# STM32F103C8T6.net
KiCad netlist of a schematic drawn in Altium Designer
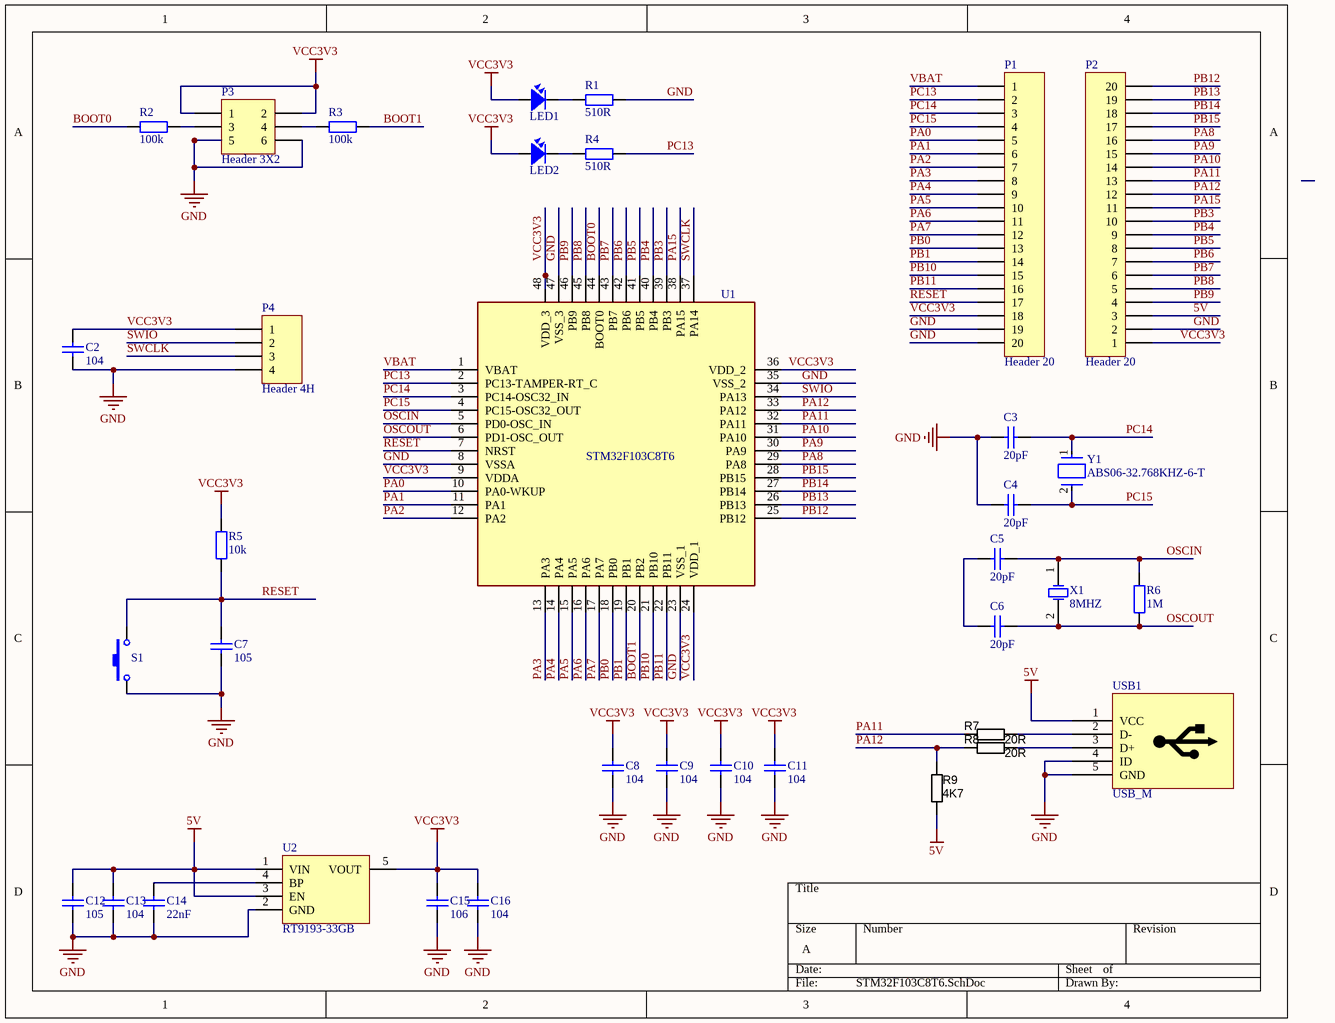
[diagram p0: STM32F103C8T6.SchDoc]

(export (version "E")
  (design (tool "Eeschema 10.0.6"))
  (components
    (comp (ref "C2")
      (value "104")
      (footprint "tu 0603")
      (description "Dán")
      (libsource (lib "Capacitor") (part "Tu 0603 104 50V 10%"))
    )
    (comp (ref "C3")
      (value "20pF")
      (footprint "tu 0805")
      (description "Dán")
      (libsource (lib "Capacitor") (part "Tu 0805 20pF 50V 10%"))
    )
    (comp (ref "C4")
      (value "20pF")
      (footprint "tu 0805")
      (description "Dán")
      (libsource (lib "Capacitor") (part "Tu 0805 20pF 50V 10%"))
    )
    (comp (ref "C5")
      (value "20pF")
      (footprint "tu 0805")
      (description "Dán")
      (libsource (lib "Capacitor") (part "Tu 0805 20pF 50V 10%"))
    )
    (comp (ref "C6")
      (value "20pF")
      (footprint "tu 0805")
      (description "Dán")
      (libsource (lib "Capacitor") (part "Tu 0805 20pF 50V 10%"))
    )
    (comp (ref "C7")
      (value "105")
      (footprint "tu 0603")
      (description "Dán")
      (libsource (lib "Capacitor") (part "Tu 0603 105 16V 20%"))
    )
    (comp (ref "C8")
      (value "104")
      (footprint "tu 0603")
      (description "Dán")
      (libsource (lib "Capacitor") (part "Tu 0603 104 50V 10%"))
    )
    (comp (ref "C9")
      (value "104")
      (footprint "tu 0603")
      (description "Dán")
      (libsource (lib "Capacitor") (part "Tu 0603 104 50V 10%"))
    )
    (comp (ref "C10")
      (value "104")
      (footprint "tu 0603")
      (description "Dán")
      (libsource (lib "Capacitor") (part "Tu 0603 104 50V 10%"))
    )
    (comp (ref "C11")
      (value "104")
      (footprint "tu 0603")
      (description "Dán")
      (libsource (lib "Capacitor") (part "Tu 0603 104 50V 10%"))
    )
    (comp (ref "C12")
      (value "105")
      (footprint "tu 0805")
      (description "Dán")
      (libsource (lib "Capacitor") (part "Tu 0805 105 50V 10%"))
    )
    (comp (ref "C13")
      (value "104")
      (footprint "tu 0603")
      (description "Dán")
      (libsource (lib "Capacitor") (part "Tu 0603 104 50V 10%"))
    )
    (comp (ref "C14")
      (value "22nF")
      (footprint "tu 0805")
      (description "Dán")
      (libsource (lib "Capacitor") (part "Tu 0805 22nF 50V 20%"))
    )
    (comp (ref "C15")
      (value "106")
      (footprint "tu 0603")
      (description "Dán")
      (libsource (lib "Capacitor") (part "Tu 0603 106 16V 20%"))
    )
    (comp (ref "C16")
      (value "104")
      (footprint "tu 0603")
      (description "Dán")
      (libsource (lib "Capacitor") (part "Tu 0603 104 50V 10%"))
    )
    (comp (ref "LED1")
      (value "LED SMD")
      (footprint "SM-LED-0805-Blue")
      (libsource (lib "syhaunguyen") (part "LED-SMD-0805"))
    )
    (comp (ref "LED2")
      (value "LED SMD")
      (footprint "SM-LED-0805-Blue")
      (libsource (lib "syhaunguyen") (part "LED-SMD-0805"))
    )
    (comp (ref "P1")
      (value "Header 20")
      (footprint "HDR1X20")
      (description "Header, 20-Pin")
      (fields (field (name "PUBLISHER") "Altium Limited"))
      (libsource (lib "KhanhBK_SCH_Library_2") (part "Header 20"))
    )
    (comp (ref "P2")
      (value "Header 20")
      (footprint "HDR1X20")
      (description "Header, 20-Pin")
      (fields (field (name "PUBLISHER") "Altium Limited"))
      (libsource (lib "") (part "Header 20_1"))
    )
    (comp (ref "P3")
      (value "Header 3X2")
      (footprint "HDR2X3")
      (description "Header, 3-Pin, Dual row")
      (fields (field (name "PUBLISHER") "Altium Limited"))
      (libsource (lib "KhanhBK_SCH_Library_2") (part "Header 3X2"))
    )
    (comp (ref "P4")
      (value "Header 4H")
      (footprint "HDR1X4H")
      (description "Header, 4-Pin, Right Angle")
      (fields (field (name "PUBLISHER") "Altium Limited"))
      (libsource (lib "KhanhBK_SCH_Library_2") (part "Header 4H"))
    )
    (comp (ref "R1")
      (value "510R")
      (footprint "tro smd 0603")
      (description "Dán")
      (libsource (lib "Resistor") (part "Tro 0603 5% 510R"))
    )
    (comp (ref "R2")
      (value "100k")
      (footprint "tro smd 0603")
      (description "Dán")
      (libsource (lib "Resistor") (part "Tro 0603 5% 100k"))
    )
    (comp (ref "R3")
      (value "100k")
      (footprint "tro smd 0603")
      (description "Dán")
      (libsource (lib "Resistor") (part "Tro 0603 5% 100k"))
    )
    (comp (ref "R4")
      (value "510R")
      (footprint "tro smd 0603")
      (description "Dán")
      (libsource (lib "Resistor") (part "Tro 0603 5% 510R"))
    )
    (comp (ref "R5")
      (value "10k")
      (footprint "tro smd 0603")
      (description "Dán")
      (libsource (lib "Resistor") (part "Tro 0603 1% 10k"))
    )
    (comp (ref "R6")
      (value "1M")
      (footprint "tro smd 0603")
      (description "Dán")
      (libsource (lib "Resistor") (part "Tro 0603 5% 1M"))
    )
    (comp (ref "R7")
      (value "20R")
      (footprint "RESC3216N")
      (description "Resistor SMD chip 20 Ohm 0.25W 5% 1206")
      (fields (field (name "TOLERANCE") "±5%") (field (name "Comment") "Thick Film"))
      (libsource (lib "PBL - Resistors") (part "RES_20R_1206_5%"))
    )
    (comp (ref "R8")
      (value "20R")
      (footprint "RESC3216N")
      (description "Resistor SMD chip 20 Ohm 0.25W 5% 1206")
      (fields (field (name "TOLERANCE") "±5%") (field (name "Comment") "Thick Film"))
      (libsource (lib "PBL - Resistors") (part "RES_20R_1206_5%"))
    )
    (comp (ref "R9")
      (value "4K7")
      (footprint "RESC1608N")
      (description "Resistor SMD chip 4.7k Ohm 0.1W 5% 0603")
      (fields (field (name "TOLERANCE") "±5%") (field (name "Comment") "Thick Film"))
      (libsource (lib "PBL - Resistors") (part "RES_4K7_0603_5%"))
    )
    (comp (ref "S1")
      (value "SW-SMD")
      (footprint "SW-SMD")
      (description "Switch")
      (fields (field (name "PUBLISHER") "Altium Limited"))
      (libsource (lib "KhanhBK_SCH_Library_2") (part "SW-SMD"))
    )
    (comp (ref "U1")
      (value "STM32F103C8T6")
      (footprint "LQFP-48_19.6_393_58X11_SMD")
      (description "ARM® Cortex®-M3 STM32F1 Microcontroller IC 32-Bit 72MHz 64KB (64K x 8) FLASH 48-LQFP (7x7)")
      (fields (field (name "MANUFACTURER") "STMicroelectronics"))
      (libsource (lib "IC") (part "IC_STM32F103C8T6"))
    )
    (comp (ref "U2")
      (value "RT9193-33GB")
      (footprint "SOT23-5")
      (description "Linear Voltage Regulator IC 1 Output 300mA SOT-23-5")
      (fields (field (name "MANUFACTURER") "Richtek USA Inc."))
      (libsource (lib "IC") (part "REG_5.5V-3.3V-0.3A-1W-SOT-23-5"))
    )
    (comp (ref "USB1")
      (value "USB_M")
      (footprint "USB_B_MINI_SMD")
      (libsource (lib "KhanhBK_SCH_Library_2") (part "USB_M"))
    )
    (comp (ref "X1")
      (value "8MHZ")
      (footprint "ABRA-ABLS-14.7456MHZ-B2-T_V")
      (description "Low Profile Crystal, 8.0 MHz, +/- 30 ppm, -20 to 70 degC, 2-Pin SMD, RoHS, Tape and Reel")
      (fields (field (name "MANUFACTURER") "ABRACON") (field (name "TOLERANCE") "30PPM"))
      (libsource (lib "Altium Content Vault") (part "XTAL_1-2-2"))
    )
    (comp (ref "Y1")
      (value "ABS06-32.768KHZ-6-T")
      (footprint "FP-ABS06-MFG")
      (description "Crystal 32.768kHz ±20ppm (Tol) 6pF FUND 90kΩ 2-Pin Mini-CSMD T/R")
      (libsource (lib "Altium Content Vault") (part "c23a69dc6c9e2f18f2079038eb95dd1"))
    )
  )
  (nets
    (net (code "1") (name "/BOOT0") (class "Default")
      (node (ref "R2") (pin "1") (pinfunction "1_1") (pintype "passive"))
      (node (ref "U1") (pin "44") (pinfunction "BOOT0_44") (pintype "passive"))
    )
    (net (code "2") (name "/BOOT1") (class "Default")
      (node (ref "R3") (pin "2") (pinfunction "2_2") (pintype "passive"))
      (node (ref "U1") (pin "20") (pinfunction "PB2_20") (pintype "passive"))
    )
    (net (code "3") (name "/OSCIN") (class "Default")
      (node (ref "C5") (pin "1") (pinfunction "1_1") (pintype "passive"))
      (node (ref "R6") (pin "2") (pinfunction "2_2") (pintype "passive"))
      (node (ref "U1") (pin "5") (pinfunction "PD0-OSC_IN_5") (pintype "passive"))
      (node (ref "X1") (pin "1") (pinfunction "X1_1") (pintype "passive"))
    )
    (net (code "4") (name "/OSCOUT") (class "Default")
      (node (ref "C6") (pin "1") (pinfunction "1_1") (pintype "passive"))
      (node (ref "R6") (pin "1") (pinfunction "1_1") (pintype "passive"))
      (node (ref "U1") (pin "6") (pinfunction "PD1-OSC_OUT_6") (pintype "passive"))
      (node (ref "X1") (pin "2") (pinfunction "X2_2") (pintype "passive"))
    )
    (net (code "5") (name "/PA0") (class "Default")
      (node (ref "P1") (pin "5") (pinfunction "5_5") (pintype "passive"))
      (node (ref "U1") (pin "10") (pinfunction "PA0-WKUP_10") (pintype "passive"))
    )
    (net (code "6") (name "/PA1") (class "Default")
      (node (ref "P1") (pin "6") (pinfunction "6_6") (pintype "passive"))
      (node (ref "U1") (pin "11") (pinfunction "PA1_11") (pintype "passive"))
    )
    (net (code "7") (name "/PA2") (class "Default")
      (node (ref "P1") (pin "7") (pinfunction "7_7") (pintype "passive"))
      (node (ref "U1") (pin "12") (pinfunction "PA2_12") (pintype "passive"))
    )
    (net (code "8") (name "/PA3") (class "Default")
      (node (ref "P1") (pin "8") (pinfunction "8_8") (pintype "passive"))
      (node (ref "U1") (pin "13") (pinfunction "PA3_13") (pintype "passive"))
    )
    (net (code "9") (name "/PA4") (class "Default")
      (node (ref "P1") (pin "9") (pinfunction "9_9") (pintype "passive"))
      (node (ref "U1") (pin "14") (pinfunction "PA4_14") (pintype "passive"))
    )
    (net (code "10") (name "/PA5") (class "Default")
      (node (ref "P1") (pin "10") (pinfunction "10_10") (pintype "passive"))
      (node (ref "U1") (pin "15") (pinfunction "PA5_15") (pintype "passive"))
    )
    (net (code "11") (name "/PA6") (class "Default")
      (node (ref "P1") (pin "11") (pinfunction "11_11") (pintype "passive"))
      (node (ref "U1") (pin "16") (pinfunction "PA6_16") (pintype "passive"))
    )
    (net (code "12") (name "/PA7") (class "Default")
      (node (ref "P1") (pin "12") (pinfunction "12_12") (pintype "passive"))
      (node (ref "U1") (pin "17") (pinfunction "PA7_17") (pintype "passive"))
    )
    (net (code "13") (name "/PA8") (class "Default")
      (node (ref "P2") (pin "16") (pinfunction "16_16") (pintype "passive"))
      (node (ref "U1") (pin "29") (pinfunction "PA8_29") (pintype "passive"))
    )
    (net (code "14") (name "/PA9") (class "Default")
      (node (ref "P2") (pin "15") (pinfunction "15_15") (pintype "passive"))
      (node (ref "U1") (pin "30") (pinfunction "PA9_30") (pintype "passive"))
    )
    (net (code "15") (name "/PA10") (class "Default")
      (node (ref "P2") (pin "14") (pinfunction "14_14") (pintype "passive"))
      (node (ref "U1") (pin "31") (pinfunction "PA10_31") (pintype "passive"))
    )
    (net (code "16") (name "/PA11") (class "Default")
      (node (ref "P2") (pin "13") (pinfunction "13_13") (pintype "passive"))
      (node (ref "R7") (pin "1") (pinfunction "1_1") (pintype "passive"))
      (node (ref "U1") (pin "32") (pinfunction "PA11_32") (pintype "passive"))
    )
    (net (code "17") (name "/PA12") (class "Default")
      (node (ref "P2") (pin "12") (pinfunction "12_12") (pintype "passive"))
      (node (ref "R8") (pin "1") (pinfunction "1_1") (pintype "passive"))
      (node (ref "R9") (pin "1") (pinfunction "1_1") (pintype "passive"))
      (node (ref "U1") (pin "33") (pinfunction "PA12_33") (pintype "passive"))
    )
    (net (code "18") (name "/PA15") (class "Default")
      (node (ref "P2") (pin "11") (pinfunction "11_11") (pintype "passive"))
      (node (ref "U1") (pin "38") (pinfunction "PA15_38") (pintype "passive"))
    )
    (net (code "19") (name "/PB0") (class "Default")
      (node (ref "P1") (pin "13") (pinfunction "13_13") (pintype "passive"))
      (node (ref "U1") (pin "18") (pinfunction "PB0_18") (pintype "passive"))
    )
    (net (code "20") (name "/PB1") (class "Default")
      (node (ref "P1") (pin "14") (pinfunction "14_14") (pintype "passive"))
      (node (ref "U1") (pin "19") (pinfunction "PB1_19") (pintype "passive"))
    )
    (net (code "21") (name "/PB3") (class "Default")
      (node (ref "P2") (pin "10") (pinfunction "10_10") (pintype "passive"))
      (node (ref "U1") (pin "39") (pinfunction "PB3_39") (pintype "passive"))
    )
    (net (code "22") (name "/PB4") (class "Default")
      (node (ref "P2") (pin "9") (pinfunction "9_9") (pintype "passive"))
      (node (ref "U1") (pin "40") (pinfunction "PB4_40") (pintype "passive"))
    )
    (net (code "23") (name "/PB5") (class "Default")
      (node (ref "P2") (pin "8") (pinfunction "8_8") (pintype "passive"))
      (node (ref "U1") (pin "41") (pinfunction "PB5_41") (pintype "passive"))
    )
    (net (code "24") (name "/PB6") (class "Default")
      (node (ref "P2") (pin "7") (pinfunction "7_7") (pintype "passive"))
      (node (ref "U1") (pin "42") (pinfunction "PB6_42") (pintype "passive"))
    )
    (net (code "25") (name "/PB7") (class "Default")
      (node (ref "P2") (pin "6") (pinfunction "6_6") (pintype "passive"))
      (node (ref "U1") (pin "43") (pinfunction "PB7_43") (pintype "passive"))
    )
    (net (code "26") (name "/PB8") (class "Default")
      (node (ref "P2") (pin "5") (pinfunction "5_5") (pintype "passive"))
      (node (ref "U1") (pin "45") (pinfunction "PB8_45") (pintype "passive"))
    )
    (net (code "27") (name "/PB9") (class "Default")
      (node (ref "P2") (pin "4") (pinfunction "4_4") (pintype "passive"))
      (node (ref "U1") (pin "46") (pinfunction "PB9_46") (pintype "passive"))
    )
    (net (code "28") (name "/PB10") (class "Default")
      (node (ref "P1") (pin "15") (pinfunction "15_15") (pintype "passive"))
      (node (ref "U1") (pin "21") (pinfunction "PB10_21") (pintype "passive"))
    )
    (net (code "29") (name "/PB11") (class "Default")
      (node (ref "P1") (pin "16") (pinfunction "16_16") (pintype "passive"))
      (node (ref "U1") (pin "22") (pinfunction "PB11_22") (pintype "passive"))
    )
    (net (code "30") (name "/PB12") (class "Default")
      (node (ref "P2") (pin "20") (pinfunction "20_20") (pintype "passive"))
      (node (ref "U1") (pin "25") (pinfunction "PB12_25") (pintype "passive"))
    )
    (net (code "31") (name "/PB13") (class "Default")
      (node (ref "P2") (pin "19") (pinfunction "19_19") (pintype "passive"))
      (node (ref "U1") (pin "26") (pinfunction "PB13_26") (pintype "passive"))
    )
    (net (code "32") (name "/PB14") (class "Default")
      (node (ref "P2") (pin "18") (pinfunction "18_18") (pintype "passive"))
      (node (ref "U1") (pin "27") (pinfunction "PB14_27") (pintype "passive"))
    )
    (net (code "33") (name "/PB15") (class "Default")
      (node (ref "P2") (pin "17") (pinfunction "17_17") (pintype "passive"))
      (node (ref "U1") (pin "28") (pinfunction "PB15_28") (pintype "passive"))
    )
    (net (code "34") (name "/PC13") (class "Default")
      (node (ref "P1") (pin "2") (pinfunction "2_2") (pintype "passive"))
      (node (ref "R4") (pin "2") (pinfunction "2_2") (pintype "passive"))
      (node (ref "U1") (pin "2") (pinfunction "PC13-TAMPER-RT_C_2") (pintype "passive"))
    )
    (net (code "35") (name "/PC14") (class "Default")
      (node (ref "C3") (pin "1") (pinfunction "1_1") (pintype "passive"))
      (node (ref "P1") (pin "3") (pinfunction "3_3") (pintype "passive"))
      (node (ref "U1") (pin "3") (pinfunction "PC14-OSC32_IN_3") (pintype "passive"))
      (node (ref "Y1") (pin "1") (pinfunction "1_1") (pintype "passive"))
    )
    (net (code "36") (name "/PC15") (class "Default")
      (node (ref "C4") (pin "1") (pinfunction "1_1") (pintype "passive"))
      (node (ref "P1") (pin "4") (pinfunction "4_4") (pintype "passive"))
      (node (ref "U1") (pin "4") (pinfunction "PC15-OSC32_OUT_4") (pintype "passive"))
      (node (ref "Y1") (pin "2") (pinfunction "2_2") (pintype "passive"))
    )
    (net (code "37") (name "/RESET") (class "Default")
      (node (ref "C7") (pin "1") (pinfunction "1_1") (pintype "passive"))
      (node (ref "P1") (pin "17") (pinfunction "17_17") (pintype "passive"))
      (node (ref "R5") (pin "1") (pinfunction "1_1") (pintype "passive"))
      (node (ref "S1") (pin "2") (pinfunction "2_2") (pintype "passive"))
      (node (ref "U1") (pin "7") (pinfunction "NRST_7") (pintype "passive"))
    )
    (net (code "38") (name "/SWCLK") (class "Default")
      (node (ref "P4") (pin "3") (pinfunction "3_3") (pintype "passive"))
      (node (ref "U1") (pin "37") (pinfunction "PA14_37") (pintype "passive"))
    )
    (net (code "39") (name "/SWIO") (class "Default")
      (node (ref "P4") (pin "2") (pinfunction "2_2") (pintype "passive"))
      (node (ref "U1") (pin "34") (pinfunction "PA13_34") (pintype "passive"))
    )
    (net (code "40") (name "/VBAT") (class "Default")
      (node (ref "P1") (pin "1") (pinfunction "1_1") (pintype "passive"))
      (node (ref "U1") (pin "1") (pinfunction "VBAT_1") (pintype "passive"))
    )
    (net (code "41") (name "5V") (class "Default")
      (node (ref "C12") (pin "1") (pinfunction "1_1") (pintype "passive"))
      (node (ref "C13") (pin "1") (pinfunction "1_1") (pintype "passive"))
      (node (ref "P2") (pin "3") (pinfunction "3_3") (pintype "passive"))
      (node (ref "R9") (pin "2") (pinfunction "2_2") (pintype "passive"))
      (node (ref "U2") (pin "1") (pinfunction "VIN_1") (pintype "passive"))
      (node (ref "U2") (pin "3") (pinfunction "EN_3") (pintype "passive"))
      (node (ref "USB1") (pin "1") (pinfunction "VCC_1") (pintype "passive"))
    )
    (net (code "42") (name "GND") (class "Default")
      (node (ref "C10") (pin "2") (pinfunction "2_2") (pintype "passive"))
      (node (ref "C11") (pin "2") (pinfunction "2_2") (pintype "passive"))
      (node (ref "C12") (pin "2") (pinfunction "2_2") (pintype "passive"))
      (node (ref "C13") (pin "2") (pinfunction "2_2") (pintype "passive"))
      (node (ref "C14") (pin "2") (pinfunction "2_2") (pintype "passive"))
      (node (ref "C15") (pin "2") (pinfunction "2_2") (pintype "passive"))
      (node (ref "C16") (pin "2") (pinfunction "2_2") (pintype "passive"))
      (node (ref "C2") (pin "2") (pinfunction "2_2") (pintype "passive"))
      (node (ref "C3") (pin "2") (pinfunction "2_2") (pintype "passive"))
      (node (ref "C4") (pin "2") (pinfunction "2_2") (pintype "passive"))
      (node (ref "C7") (pin "2") (pinfunction "2_2") (pintype "passive"))
      (node (ref "C8") (pin "2") (pinfunction "2_2") (pintype "passive"))
      (node (ref "C9") (pin "2") (pinfunction "2_2") (pintype "passive"))
      (node (ref "P1") (pin "19") (pinfunction "19_19") (pintype "passive"))
      (node (ref "P1") (pin "20") (pinfunction "20_20") (pintype "passive"))
      (node (ref "P2") (pin "2") (pinfunction "2_2") (pintype "passive"))
      (node (ref "P3") (pin "5") (pinfunction "5_5") (pintype "passive"))
      (node (ref "P3") (pin "6") (pinfunction "6_6") (pintype "passive"))
      (node (ref "P4") (pin "4") (pinfunction "4_4") (pintype "passive"))
      (node (ref "R1") (pin "2") (pinfunction "2_2") (pintype "passive"))
      (node (ref "S1") (pin "1") (pinfunction "1_1") (pintype "passive"))
      (node (ref "U1") (pin "23") (pinfunction "VSS_1_23") (pintype "passive"))
      (node (ref "U1") (pin "35") (pinfunction "VSS_2_35") (pintype "passive"))
      (node (ref "U1") (pin "47") (pinfunction "VSS_3_47") (pintype "passive"))
      (node (ref "U1") (pin "8") (pinfunction "VSSA_8") (pintype "passive"))
      (node (ref "U2") (pin "2") (pinfunction "GND_2") (pintype "passive"))
      (node (ref "USB1") (pin "4") (pinfunction "ID_4") (pintype "passive"))
      (node (ref "USB1") (pin "5") (pinfunction "GND_5") (pintype "passive"))
    )
    (net (code "43") (name "Net-(C5-Pad2)") (class "Default")
      (node (ref "C5") (pin "2") (pinfunction "2_2") (pintype "passive"))
      (node (ref "C6") (pin "2") (pinfunction "2_2") (pintype "passive"))
    )
    (net (code "44") (name "Net-(LED1-Pad2)") (class "Default")
      (node (ref "LED1") (pin "2") (pinfunction "2_2") (pintype "passive"))
      (node (ref "R1") (pin "1") (pinfunction "1_1") (pintype "passive"))
    )
    (net (code "45") (name "Net-(LED2-Pad2)") (class "Default")
      (node (ref "LED2") (pin "2") (pinfunction "2_2") (pintype "passive"))
      (node (ref "R4") (pin "1") (pinfunction "1_1") (pintype "passive"))
    )
    (net (code "46") (name "Net-(P3-Pad3)") (class "Default")
      (node (ref "P3") (pin "3") (pinfunction "3_3") (pintype "passive"))
      (node (ref "R2") (pin "2") (pinfunction "2_2") (pintype "passive"))
    )
    (net (code "47") (name "Net-(P3-Pad4)") (class "Default")
      (node (ref "P3") (pin "4") (pinfunction "4_4") (pintype "passive"))
      (node (ref "R3") (pin "1") (pinfunction "1_1") (pintype "passive"))
    )
    (net (code "48") (name "Net-(U2-BP)") (class "Default")
      (node (ref "C14") (pin "1") (pinfunction "1_1") (pintype "passive"))
      (node (ref "U2") (pin "4") (pinfunction "BP_4") (pintype "passive"))
    )
    (net (code "49") (name "Net-(USB1-D+)") (class "Default")
      (node (ref "R8") (pin "2") (pinfunction "2_2") (pintype "passive"))
      (node (ref "USB1") (pin "3") (pinfunction "D+_3") (pintype "passive"))
    )
    (net (code "50") (name "Net-(USB1-D-)") (class "Default")
      (node (ref "R7") (pin "2") (pinfunction "2_2") (pintype "passive"))
      (node (ref "USB1") (pin "2") (pinfunction "D-_2") (pintype "passive"))
    )
    (net (code "51") (name "VCC3V3") (class "Default")
      (node (ref "C10") (pin "1") (pinfunction "1_1") (pintype "passive"))
      (node (ref "C11") (pin "1") (pinfunction "1_1") (pintype "passive"))
      (node (ref "C15") (pin "1") (pinfunction "1_1") (pintype "passive"))
      (node (ref "C16") (pin "1") (pinfunction "1_1") (pintype "passive"))
      (node (ref "C2") (pin "1") (pinfunction "1_1") (pintype "passive"))
      (node (ref "C8") (pin "1") (pinfunction "1_1") (pintype "passive"))
      (node (ref "C9") (pin "1") (pinfunction "1_1") (pintype "passive"))
      (node (ref "LED1") (pin "1") (pinfunction "1_1") (pintype "passive"))
      (node (ref "LED2") (pin "1") (pinfunction "1_1") (pintype "passive"))
      (node (ref "P1") (pin "18") (pinfunction "18_18") (pintype "passive"))
      (node (ref "P2") (pin "1") (pinfunction "1_1") (pintype "passive"))
      (node (ref "P3") (pin "1") (pinfunction "1_1") (pintype "passive"))
      (node (ref "P3") (pin "2") (pinfunction "2_2") (pintype "passive"))
      (node (ref "P4") (pin "1") (pinfunction "1_1") (pintype "passive"))
      (node (ref "R5") (pin "2") (pinfunction "2_2") (pintype "passive"))
      (node (ref "U1") (pin "24") (pinfunction "VDD_1_24") (pintype "passive"))
      (node (ref "U1") (pin "36") (pinfunction "VDD_2_36") (pintype "passive"))
      (node (ref "U1") (pin "48") (pinfunction "VDD_3_48") (pintype "passive"))
      (node (ref "U1") (pin "9") (pinfunction "VDDA_9") (pintype "passive"))
      (node (ref "U2") (pin "5") (pinfunction "VOUT_5") (pintype "passive"))
    )
  )
)
